# 01_MCU.net
KiCad netlist of a schematic drawn in Altium Designer
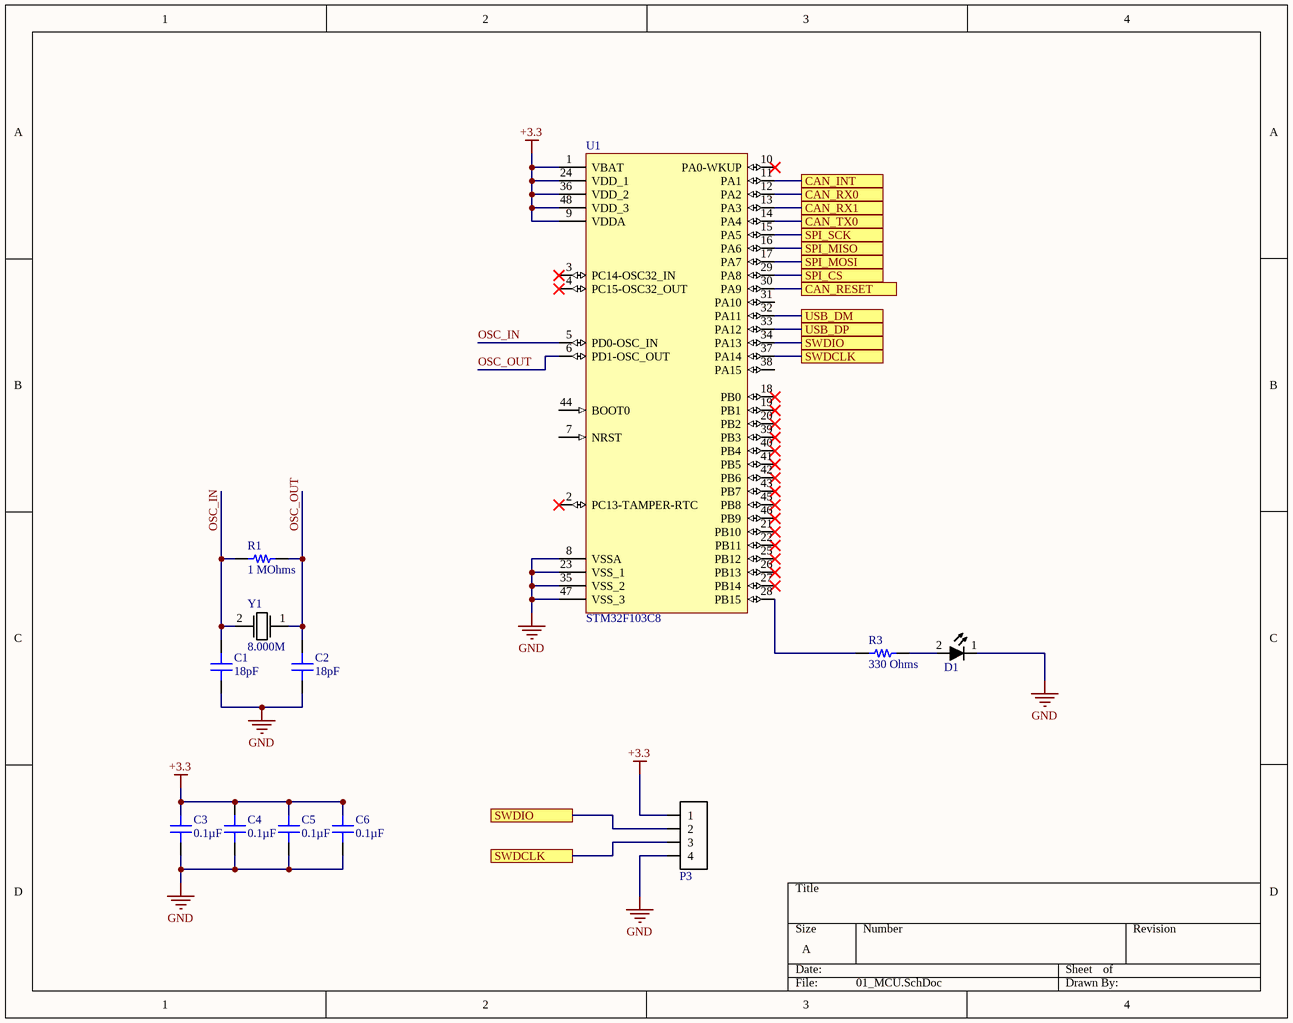
[diagram p0: 01_MCU.SchDoc]

(export (version "E")
  (design (tool "Eeschema 10.0.6"))
  (components
    (comp (ref "C1")
      (value "18pF")
      (footprint "CAP 0603_1608")
      (description "CAP CER 18PF 50V C0G/NP0 0603")
      (fields (field (name "PART NUMBER") "C0603X180J5GACTU") (field (name "MANUFACTURER") "KEMET"))
      (libsource (lib "Celestial Altium Library - altium_library") (part "Capacitor"))
    )
    (comp (ref "C2")
      (value "18pF")
      (footprint "CAP 0603_1608")
      (description "CAP CER 18PF 50V C0G/NP0 0603")
      (fields (field (name "PART NUMBER") "C0603X180J5GACTU") (field (name "MANUFACTURER") "KEMET"))
      (libsource (lib "Celestial Altium Library - altium_library") (part "Capacitor"))
    )
    (comp (ref "C3")
      (value "0.1µF")
      (footprint "CAP 0805_2012")
      (description "CAP CER 0805 0.1UF 50V X7R")
      (fields (field (name "PART NUMBER") "C0805X104K5RAC3316") (field (name "MANUFACTURER") "KEMET"))
      (libsource (lib "Celestial Altium Library - altium_library") (part "Capacitor"))
    )
    (comp (ref "C4")
      (value "0.1µF")
      (footprint "CAP 0805_2012")
      (description "CAP CER 0805 0.1UF 50V X7R")
      (fields (field (name "PART NUMBER") "C0805X104K5RAC3316") (field (name "MANUFACTURER") "KEMET"))
      (libsource (lib "Celestial Altium Library - altium_library") (part "Capacitor"))
    )
    (comp (ref "C5")
      (value "0.1µF")
      (footprint "CAP 0805_2012")
      (description "CAP CER 0805 0.1UF 50V X7R")
      (fields (field (name "PART NUMBER") "C0805X104K5RAC3316") (field (name "MANUFACTURER") "KEMET"))
      (libsource (lib "Celestial Altium Library - altium_library") (part "Capacitor"))
    )
    (comp (ref "C6")
      (value "0.1µF")
      (footprint "CAP 0805_2012")
      (description "CAP CER 0805 0.1UF 50V X7R")
      (fields (field (name "PART NUMBER") "C0805X104K5RAC3316") (field (name "MANUFACTURER") "KEMET"))
      (libsource (lib "Celestial Altium Library - altium_library") (part "Capacitor"))
    )
    (comp (ref "D1")
      (value "diode_4")
      (footprint "chip_0603_LED")
      (description "LED, Blue, 0603, Low current, HELI2 Series")
      (fields (field (name "PART NUMBER") "DIO-00049") (field (name "MANUFACTURER") "Kingbright"))
      (libsource (lib "cwrubotix_library") (part "diode_4"))
    )
    (comp (ref "P3")
      (value "conn-4x1_0")
      (footprint "HDDR_4x1_0")
      (description "Header 4x1, 0.1\"")
      (fields (field (name "PART NUMBER") "CONN-00029"))
      (libsource (lib "Connectors") (part "conn-4x1_0"))
    )
    (comp (ref "R1")
      (value "1 MOhms")
      (footprint "RES 0603_1608")
      (description "RES SMD 1M OHM 1% 1/4W 0603")
      (fields (field (name "PART NUMBER") "RCS06031M00FKEA") (field (name "MANUFACTURER") "Vishay Dale"))
      (libsource (lib "Celestial Altium Library - altium_library") (part "Resistor"))
    )
    (comp (ref "R3")
      (value "330 Ohms")
      (footprint "RES 0603_1608")
      (description "RES 330 OHM 5% 1/8W 0603")
      (fields
        (field (name "PART NUMBER") "RK73B1JTTD331J")
        (field (name "MANUFACTURER") "KOA Speer Electronics, Inc.")
      )
      (libsource (lib "Celestial Altium Library - altium_library") (part "Resistor"))
    )
    (comp (ref "U1")
      (value "STM32F103C8")
      (footprint "LQFP48_0")
      (description "STM32 M3, LQFP-48")
      (fields (field (name "PART NUMBER") "UCTRL-00008") (field (name "MANUFACTURER") "ST"))
      (libsource (lib "cwrubotix_library") (part "STM32F103C8"))
    )
    (comp (ref "Y1")
      (value "osc_xtal_2p_0")
      (footprint "ABLS_AT49_OSC")
      (description "XTAL, 8MHz, 18pF, 20ppm")
      (fields
        (field (name "TOLERANCE") "20ppm")
        (field (name "FREQUENCY") "8.000M")
        (field (name "PART NUMBER") "OSC-00002")
      )
      (libsource (lib "Oscillators") (part "osc_xtal_2p_0"))
    )
  )
  (nets
    (net (code "1") (name "+3.3") (class "Default")
      (node (ref "C3") (pin "2") (pinfunction "2_2") (pintype "passive"))
      (node (ref "C4") (pin "2") (pinfunction "2_2") (pintype "passive"))
      (node (ref "C5") (pin "2") (pinfunction "2_2") (pintype "passive"))
      (node (ref "C6") (pin "2") (pinfunction "2_2") (pintype "passive"))
      (node (ref "P3") (pin "1") (pinfunction "1_1") (pintype "passive"))
      (node (ref "U1") (pin "1") (pinfunction "VBAT_1") (pintype "passive"))
      (node (ref "U1") (pin "24") (pinfunction "VDD_1_24") (pintype "power_in"))
      (node (ref "U1") (pin "36") (pinfunction "VDD_2_36") (pintype "power_in"))
      (node (ref "U1") (pin "48") (pinfunction "VDD_3_48") (pintype "power_in"))
      (node (ref "U1") (pin "9") (pinfunction "VDDA_9") (pintype "power_in"))
    )
    (net (code "2") (name "/CAN_INT") (class "Default")
      (node (ref "U1") (pin "11") (pinfunction "PA1_11") (pintype "bidirectional"))
    )
    (net (code "3") (name "/CAN_RESET") (class "Default")
      (node (ref "U1") (pin "30") (pinfunction "PA9_30") (pintype "bidirectional"))
    )
    (net (code "4") (name "/CAN_RX0") (class "Default")
      (node (ref "U1") (pin "12") (pinfunction "PA2_12") (pintype "bidirectional"))
    )
    (net (code "5") (name "/CAN_RX1") (class "Default")
      (node (ref "U1") (pin "13") (pinfunction "PA3_13") (pintype "bidirectional"))
    )
    (net (code "6") (name "/CAN_TX0") (class "Default")
      (node (ref "U1") (pin "14") (pinfunction "PA4_14") (pintype "bidirectional"))
    )
    (net (code "7") (name "/OSC_IN") (class "Default")
      (node (ref "C1") (pin "2") (pinfunction "2_2") (pintype "passive"))
      (node (ref "R1") (pin "1") (pinfunction "1_1") (pintype "passive"))
      (node (ref "U1") (pin "5") (pinfunction "PD0-OSC_IN_5") (pintype "bidirectional"))
      (node (ref "Y1") (pin "2") (pinfunction "20_2") (pintype "passive"))
    )
    (net (code "8") (name "/OSC_OUT") (class "Default")
      (node (ref "C2") (pin "2") (pinfunction "2_2") (pintype "passive"))
      (node (ref "R1") (pin "2") (pinfunction "2_2") (pintype "passive"))
      (node (ref "U1") (pin "6") (pinfunction "PD1-OSC_OUT_6") (pintype "bidirectional"))
      (node (ref "Y1") (pin "1") (pinfunction "20_1") (pintype "passive"))
    )
    (net (code "9") (name "/SPI_CS") (class "Default")
      (node (ref "U1") (pin "29") (pinfunction "PA8_29") (pintype "bidirectional"))
    )
    (net (code "10") (name "/SPI_MISO") (class "Default")
      (node (ref "U1") (pin "16") (pinfunction "PA6_16") (pintype "bidirectional"))
    )
    (net (code "11") (name "/SPI_MOSI") (class "Default")
      (node (ref "U1") (pin "17") (pinfunction "PA7_17") (pintype "bidirectional"))
    )
    (net (code "12") (name "/SPI_SCK") (class "Default")
      (node (ref "U1") (pin "15") (pinfunction "PA5_15") (pintype "bidirectional"))
    )
    (net (code "13") (name "/SWDCLK") (class "Default")
      (node (ref "P3") (pin "3") (pinfunction "3_3") (pintype "passive"))
      (node (ref "U1") (pin "37") (pinfunction "PA14_37") (pintype "bidirectional"))
    )
    (net (code "14") (name "/SWDIO") (class "Default")
      (node (ref "P3") (pin "2") (pinfunction "2_2") (pintype "passive"))
      (node (ref "U1") (pin "34") (pinfunction "PA13_34") (pintype "bidirectional"))
    )
    (net (code "15") (name "/USB_DM") (class "Default")
      (node (ref "U1") (pin "32") (pinfunction "PA11_32") (pintype "bidirectional"))
    )
    (net (code "16") (name "/USB_DP") (class "Default")
      (node (ref "U1") (pin "33") (pinfunction "PA12_33") (pintype "bidirectional"))
    )
    (net (code "17") (name "GND") (class "Default")
      (node (ref "C1") (pin "1") (pinfunction "1_1") (pintype "passive"))
      (node (ref "C2") (pin "1") (pinfunction "1_1") (pintype "passive"))
      (node (ref "C3") (pin "1") (pinfunction "1_1") (pintype "passive"))
      (node (ref "C4") (pin "1") (pinfunction "1_1") (pintype "passive"))
      (node (ref "C5") (pin "1") (pinfunction "1_1") (pintype "passive"))
      (node (ref "C6") (pin "1") (pinfunction "1_1") (pintype "passive"))
      (node (ref "D1") (pin "1") (pinfunction "1_1") (pintype "passive"))
      (node (ref "P3") (pin "4") (pinfunction "4_4") (pintype "passive"))
      (node (ref "U1") (pin "23") (pinfunction "VSS_1_23") (pintype "power_in"))
      (node (ref "U1") (pin "35") (pinfunction "VSS_2_35") (pintype "power_in"))
      (node (ref "U1") (pin "47") (pinfunction "VSS_3_47") (pintype "power_in"))
      (node (ref "U1") (pin "8") (pinfunction "VSSA_8") (pintype "power_in"))
    )
    (net (code "18") (name "Net-(D1-Pad2)") (class "Default")
      (node (ref "D1") (pin "2") (pinfunction "2_2") (pintype "passive"))
      (node (ref "R3") (pin "2") (pinfunction "2_2") (pintype "passive"))
    )
    (net (code "19") (name "Net-(U1-PB15)") (class "Default")
      (node (ref "R3") (pin "1") (pinfunction "1_1") (pintype "passive"))
      (node (ref "U1") (pin "28") (pinfunction "PB15_28") (pintype "bidirectional"))
    )
    (net (code "20") (name "unconnected-(U1-BOOT0-Pad44)") (class "Default")
      (node (ref "U1") (pin "44") (pinfunction "BOOT0_44") (pintype "input"))
    )
    (net (code "21") (name "unconnected-(U1-NRST-Pad7)") (class "Default")
      (node (ref "U1") (pin "7") (pinfunction "NRST_7") (pintype "input"))
    )
    (net (code "22") (name "unconnected-(U1-PA0-WKUP-Pad10)") (class "Default")
      (node (ref "U1") (pin "10") (pinfunction "PA0-WKUP_10") (pintype "bidirectional+no_connect"))
    )
    (net (code "23") (name "unconnected-(U1-PA10-Pad31)") (class "Default")
      (node (ref "U1") (pin "31") (pinfunction "PA10_31") (pintype "bidirectional"))
    )
    (net (code "24") (name "unconnected-(U1-PA15-Pad38)") (class "Default")
      (node (ref "U1") (pin "38") (pinfunction "PA15_38") (pintype "bidirectional"))
    )
    (net (code "25") (name "unconnected-(U1-PB0-Pad18)") (class "Default")
      (node (ref "U1") (pin "18") (pinfunction "PB0_18") (pintype "bidirectional+no_connect"))
    )
    (net (code "26") (name "unconnected-(U1-PB1-Pad19)") (class "Default")
      (node (ref "U1") (pin "19") (pinfunction "PB1_19") (pintype "bidirectional+no_connect"))
    )
    (net (code "27") (name "unconnected-(U1-PB2-Pad20)") (class "Default")
      (node (ref "U1") (pin "20") (pinfunction "PB2_20") (pintype "bidirectional+no_connect"))
    )
    (net (code "28") (name "unconnected-(U1-PB3-Pad39)") (class "Default")
      (node (ref "U1") (pin "39") (pinfunction "PB3_39") (pintype "bidirectional+no_connect"))
    )
    (net (code "29") (name "unconnected-(U1-PB4-Pad40)") (class "Default")
      (node (ref "U1") (pin "40") (pinfunction "PB4_40") (pintype "bidirectional+no_connect"))
    )
    (net (code "30") (name "unconnected-(U1-PB5-Pad41)") (class "Default")
      (node (ref "U1") (pin "41") (pinfunction "PB5_41") (pintype "bidirectional+no_connect"))
    )
    (net (code "31") (name "unconnected-(U1-PB6-Pad42)") (class "Default")
      (node (ref "U1") (pin "42") (pinfunction "PB6_42") (pintype "bidirectional+no_connect"))
    )
    (net (code "32") (name "unconnected-(U1-PB7-Pad43)") (class "Default")
      (node (ref "U1") (pin "43") (pinfunction "PB7_43") (pintype "bidirectional+no_connect"))
    )
    (net (code "33") (name "unconnected-(U1-PB8-Pad45)") (class "Default")
      (node (ref "U1") (pin "45") (pinfunction "PB8_45") (pintype "bidirectional+no_connect"))
    )
    (net (code "34") (name "unconnected-(U1-PB9-Pad46)") (class "Default")
      (node (ref "U1") (pin "46") (pinfunction "PB9_46") (pintype "bidirectional+no_connect"))
    )
    (net (code "35") (name "unconnected-(U1-PB10-Pad21)") (class "Default")
      (node (ref "U1") (pin "21") (pinfunction "PB10_21") (pintype "bidirectional+no_connect"))
    )
    (net (code "36") (name "unconnected-(U1-PB11-Pad22)") (class "Default")
      (node (ref "U1") (pin "22") (pinfunction "PB11_22") (pintype "bidirectional+no_connect"))
    )
    (net (code "37") (name "unconnected-(U1-PB12-Pad25)") (class "Default")
      (node (ref "U1") (pin "25") (pinfunction "PB12_25") (pintype "bidirectional+no_connect"))
    )
    (net (code "38") (name "unconnected-(U1-PB13-Pad26)") (class "Default")
      (node (ref "U1") (pin "26") (pinfunction "PB13_26") (pintype "bidirectional+no_connect"))
    )
    (net (code "39") (name "unconnected-(U1-PB14-Pad27)") (class "Default")
      (node (ref "U1") (pin "27") (pinfunction "PB14_27") (pintype "bidirectional+no_connect"))
    )
    (net (code "40") (name "unconnected-(U1-PC13-TAMPER-RTC-Pad2)") (class "Default")
      (node (ref "U1") (pin "2") (pinfunction "PC13-TAMPER-RTC_2") (pintype "bidirectional+no_connect"))
    )
    (net (code "41") (name "unconnected-(U1-PC14-OSC32_IN-Pad3)") (class "Default")
      (node (ref "U1") (pin "3") (pinfunction "PC14-OSC32_IN_3") (pintype "bidirectional+no_connect"))
    )
    (net (code "42") (name "unconnected-(U1-PC15-OSC32_OUT-Pad4)") (class "Default")
      (node (ref "U1") (pin "4") (pinfunction "PC15-OSC32_OUT_4") (pintype "bidirectional+no_connect"))
    )
  )
)
